# R141X.net
KiCad netlist of a schematic drawn in EAGLE
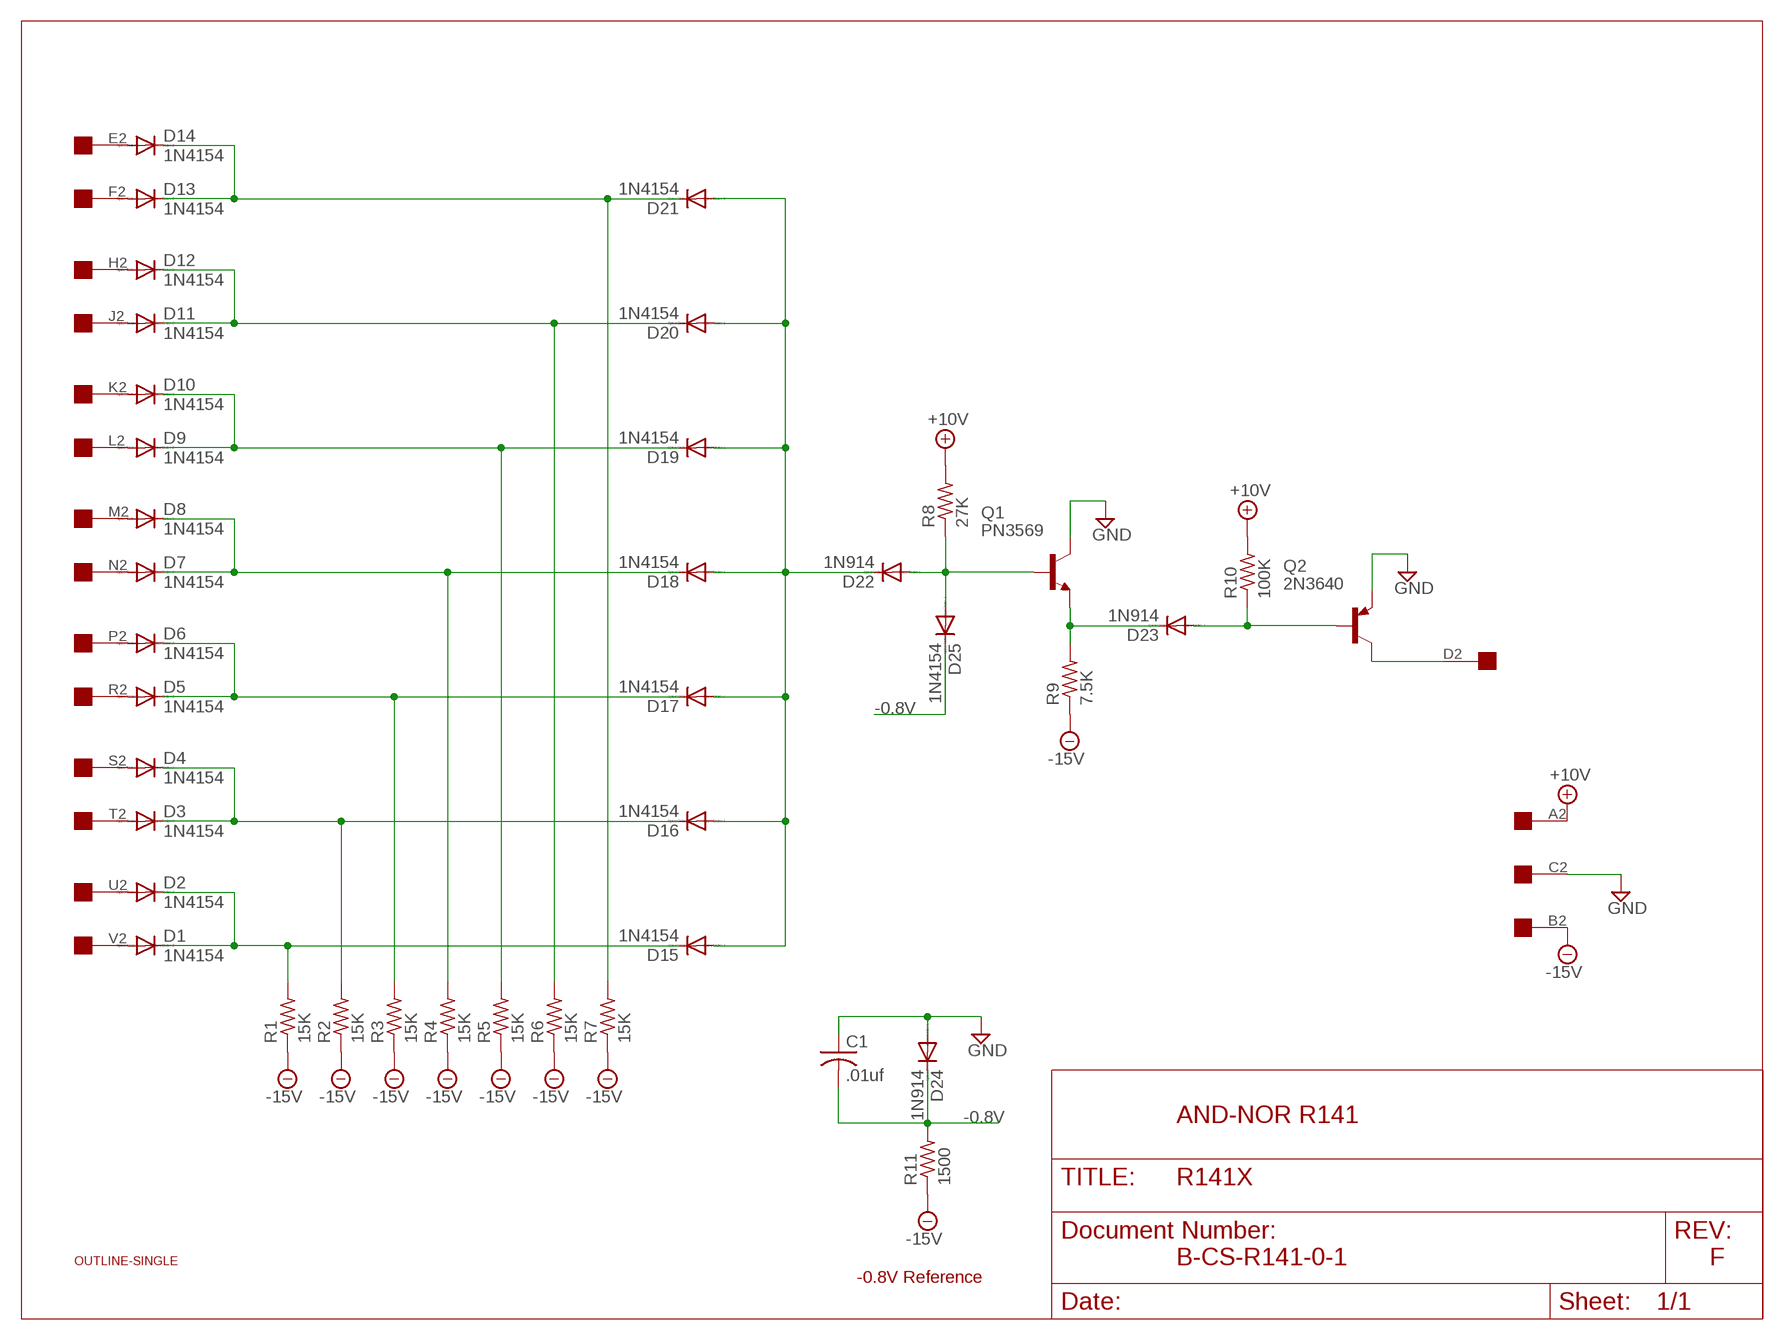
[diagram p0: schematic, sheet 1]

(export (version "E")
  (design (tool "Eeschema 10.0.6"))
  (components
    (comp (ref "C1")
      (value ".01uf")
      (footprint "eagle-import:C050-025X075")
      (libsource (lib "eagle-import") (part "C-US050-025X075"))
    )
    (comp (ref "D1")
      (value "1N4154")
      (footprint "eagle-import:DO35-10")
      (libsource (lib "eagle-import") (part "1N4148DO35-10"))
    )
    (comp (ref "D2")
      (value "1N4154")
      (footprint "eagle-import:DO35-10")
      (libsource (lib "eagle-import") (part "1N4148DO35-10"))
    )
    (comp (ref "D3")
      (value "1N4154")
      (footprint "eagle-import:DO35-10")
      (libsource (lib "eagle-import") (part "1N4148DO35-10"))
    )
    (comp (ref "D4")
      (value "1N4154")
      (footprint "eagle-import:DO35-10")
      (libsource (lib "eagle-import") (part "1N4148DO35-10"))
    )
    (comp (ref "D5")
      (value "1N4154")
      (footprint "eagle-import:DO35-10")
      (libsource (lib "eagle-import") (part "1N4148DO35-10"))
    )
    (comp (ref "D6")
      (value "1N4154")
      (footprint "eagle-import:DO35-10")
      (libsource (lib "eagle-import") (part "1N4148DO35-10"))
    )
    (comp (ref "D7")
      (value "1N4154")
      (footprint "eagle-import:DO35-10")
      (libsource (lib "eagle-import") (part "1N4148DO35-10"))
    )
    (comp (ref "D8")
      (value "1N4154")
      (footprint "eagle-import:DO35-10")
      (libsource (lib "eagle-import") (part "1N4148DO35-10"))
    )
    (comp (ref "D9")
      (value "1N4154")
      (footprint "eagle-import:DO35-10")
      (libsource (lib "eagle-import") (part "1N4148DO35-10"))
    )
    (comp (ref "D10")
      (value "1N4154")
      (footprint "eagle-import:DO35-10")
      (libsource (lib "eagle-import") (part "1N4148DO35-10"))
    )
    (comp (ref "D11")
      (value "1N4154")
      (footprint "eagle-import:DO35-10")
      (libsource (lib "eagle-import") (part "1N4148DO35-10"))
    )
    (comp (ref "D12")
      (value "1N4154")
      (footprint "eagle-import:DO35-10")
      (libsource (lib "eagle-import") (part "1N4148DO35-10"))
    )
    (comp (ref "D13")
      (value "1N4154")
      (footprint "eagle-import:DO35-10")
      (libsource (lib "eagle-import") (part "1N4148DO35-10"))
    )
    (comp (ref "D14")
      (value "1N4154")
      (footprint "eagle-import:DO35-10")
      (libsource (lib "eagle-import") (part "1N4148DO35-10"))
    )
    (comp (ref "D15")
      (value "1N4154")
      (footprint "eagle-import:DO35-10")
      (libsource (lib "eagle-import") (part "1N4148DO35-10"))
    )
    (comp (ref "D16")
      (value "1N4154")
      (footprint "eagle-import:DO35-10")
      (libsource (lib "eagle-import") (part "1N4148DO35-10"))
    )
    (comp (ref "D17")
      (value "1N4154")
      (footprint "eagle-import:DO35-10")
      (libsource (lib "eagle-import") (part "1N4148DO35-10"))
    )
    (comp (ref "D18")
      (value "1N4154")
      (footprint "eagle-import:DO35-10")
      (libsource (lib "eagle-import") (part "1N4148DO35-10"))
    )
    (comp (ref "D19")
      (value "1N4154")
      (footprint "eagle-import:DO35-10")
      (libsource (lib "eagle-import") (part "1N4148DO35-10"))
    )
    (comp (ref "D20")
      (value "1N4154")
      (footprint "eagle-import:DO35-10")
      (libsource (lib "eagle-import") (part "1N4148DO35-10"))
    )
    (comp (ref "D21")
      (value "1N4154")
      (footprint "eagle-import:DO35-10")
      (libsource (lib "eagle-import") (part "1N4148DO35-10"))
    )
    (comp (ref "D22")
      (value "1N914")
      (footprint "eagle-import:DO35-10")
      (libsource (lib "eagle-import") (part "1N4148DO35-10"))
    )
    (comp (ref "D23")
      (value "1N914")
      (footprint "eagle-import:DO35-10")
      (libsource (lib "eagle-import") (part "1N4148DO35-10"))
    )
    (comp (ref "D24")
      (value "1N914")
      (footprint "eagle-import:DO35-10")
      (libsource (lib "eagle-import") (part "1N4148DO35-10"))
    )
    (comp (ref "D25")
      (value "1N4154")
      (footprint "eagle-import:DO35-10")
      (libsource (lib "eagle-import") (part "1N4148DO35-10"))
    )
    (comp (ref "Q1")
      (value "PN3569")
      (footprint "eagle-import:TO39")
      (libsource (lib "eagle-import") (part "-NPN-TO39-EBC2N3019"))
    )
    (comp (ref "Q2")
      (value "2N3640")
      (footprint "eagle-import:TO39")
      (libsource (lib "eagle-import") (part "2N3637"))
    )
    (comp (ref "R1")
      (value "15K")
      (footprint "eagle-import:0207_10")
      (libsource (lib "eagle-import") (part "R-US_0207/10"))
    )
    (comp (ref "R2")
      (value "15K")
      (footprint "eagle-import:0207_10")
      (libsource (lib "eagle-import") (part "R-US_0207/10"))
    )
    (comp (ref "R3")
      (value "15K")
      (footprint "eagle-import:0207_10")
      (libsource (lib "eagle-import") (part "R-US_0207/10"))
    )
    (comp (ref "R4")
      (value "15K")
      (footprint "eagle-import:0207_10")
      (libsource (lib "eagle-import") (part "R-US_0207/10"))
    )
    (comp (ref "R5")
      (value "15K")
      (footprint "eagle-import:0207_10")
      (libsource (lib "eagle-import") (part "R-US_0207/10"))
    )
    (comp (ref "R6")
      (value "15K")
      (footprint "eagle-import:0207_10")
      (libsource (lib "eagle-import") (part "R-US_0207/10"))
    )
    (comp (ref "R7")
      (value "15K")
      (footprint "eagle-import:0207_10")
      (libsource (lib "eagle-import") (part "R-US_0207/10"))
    )
    (comp (ref "R8")
      (value "27K")
      (footprint "eagle-import:0207_10")
      (libsource (lib "eagle-import") (part "R-US_0207/10"))
    )
    (comp (ref "R9")
      (value "7.5K")
      (footprint "eagle-import:0207_10")
      (libsource (lib "eagle-import") (part "R-US_0207/10"))
    )
    (comp (ref "R10")
      (value "100K")
      (footprint "eagle-import:0207_10")
      (libsource (lib "eagle-import") (part "R-US_0207/10"))
    )
    (comp (ref "R11")
      (value "1500")
      (footprint "eagle-import:0207_10")
      (libsource (lib "eagle-import") (part "R-US_0207/10"))
    )
    (comp (ref "U$1")
      (value "OUTLINE-SINGLE")
      (footprint "eagle-import:SINGLE")
      (libsource (lib "eagle-import") (part "OUTLINE-SINGLE"))
    )
    (comp (ref "U$2")
      (value "EDGE-1")
      (footprint "eagle-import:EDGE-CON1")
      (libsource (lib "eagle-import") (part "EDGE-1"))
    )
  )
  (nets
    (net (code "1") (name "+10V") (class "Default")
      (node (ref "R10") (pin "2") (pinfunction "2_2") (pintype "passive"))
      (node (ref "R8") (pin "2") (pinfunction "2_2") (pintype "passive"))
      (node (ref "U$2") (pin "A2") (pinfunction "1_A2") (pintype "bidirectional"))
    )
    (net (code "2") (name "-15V") (class "Default")
      (node (ref "R1") (pin "1") (pinfunction "1_1") (pintype "passive"))
      (node (ref "R11") (pin "1") (pinfunction "1_1") (pintype "passive"))
      (node (ref "R2") (pin "1") (pinfunction "1_1") (pintype "passive"))
      (node (ref "R3") (pin "1") (pinfunction "1_1") (pintype "passive"))
      (node (ref "R4") (pin "1") (pinfunction "1_1") (pintype "passive"))
      (node (ref "R5") (pin "1") (pinfunction "1_1") (pintype "passive"))
      (node (ref "R6") (pin "1") (pinfunction "1_1") (pintype "passive"))
      (node (ref "R7") (pin "1") (pinfunction "1_1") (pintype "passive"))
      (node (ref "R9") (pin "1") (pinfunction "1_1") (pintype "passive"))
      (node (ref "U$2") (pin "B2") (pinfunction "1_B2") (pintype "bidirectional"))
    )
    (net (code "3") (name "/-0.8V") (class "Default")
      (node (ref "C1") (pin "2") (pinfunction "2_2") (pintype "passive"))
      (node (ref "D24") (pin "C") (pinfunction "C_C") (pintype "passive"))
      (node (ref "D25") (pin "C") (pinfunction "C_C") (pintype "passive"))
      (node (ref "R11") (pin "2") (pinfunction "2_2") (pintype "passive"))
    )
    (net (code "4") (name "GND") (class "Default")
      (node (ref "C1") (pin "1") (pinfunction "1_1") (pintype "passive"))
      (node (ref "D24") (pin "A") (pinfunction "A_A") (pintype "passive"))
      (node (ref "Q1") (pin "3") (pinfunction "C_3") (pintype "passive"))
      (node (ref "Q2") (pin "1") (pinfunction "E_1") (pintype "passive"))
      (node (ref "U$2") (pin "C2") (pinfunction "1_C2") (pintype "bidirectional"))
    )
    (net (code "5") (name "Net-(D1-PadC)") (class "Default")
      (node (ref "D1") (pin "C") (pinfunction "C_C") (pintype "passive"))
      (node (ref "D15") (pin "C") (pinfunction "C_C") (pintype "passive"))
      (node (ref "D2") (pin "C") (pinfunction "C_C") (pintype "passive"))
      (node (ref "R1") (pin "2") (pinfunction "2_2") (pintype "passive"))
    )
    (net (code "6") (name "Net-(D10-PadC)") (class "Default")
      (node (ref "D10") (pin "C") (pinfunction "C_C") (pintype "passive"))
      (node (ref "D19") (pin "C") (pinfunction "C_C") (pintype "passive"))
      (node (ref "D9") (pin "C") (pinfunction "C_C") (pintype "passive"))
      (node (ref "R5") (pin "2") (pinfunction "2_2") (pintype "passive"))
    )
    (net (code "7") (name "Net-(D11-PadC)") (class "Default")
      (node (ref "D11") (pin "C") (pinfunction "C_C") (pintype "passive"))
      (node (ref "D12") (pin "C") (pinfunction "C_C") (pintype "passive"))
      (node (ref "D20") (pin "C") (pinfunction "C_C") (pintype "passive"))
      (node (ref "R6") (pin "2") (pinfunction "2_2") (pintype "passive"))
    )
    (net (code "8") (name "Net-(D13-PadC)") (class "Default")
      (node (ref "D13") (pin "C") (pinfunction "C_C") (pintype "passive"))
      (node (ref "D14") (pin "C") (pinfunction "C_C") (pintype "passive"))
      (node (ref "D21") (pin "C") (pinfunction "C_C") (pintype "passive"))
      (node (ref "R7") (pin "2") (pinfunction "2_2") (pintype "passive"))
    )
    (net (code "9") (name "Net-(D15-PadA)") (class "Default")
      (node (ref "D15") (pin "A") (pinfunction "A_A") (pintype "passive"))
      (node (ref "D16") (pin "A") (pinfunction "A_A") (pintype "passive"))
      (node (ref "D17") (pin "A") (pinfunction "A_A") (pintype "passive"))
      (node (ref "D18") (pin "A") (pinfunction "A_A") (pintype "passive"))
      (node (ref "D19") (pin "A") (pinfunction "A_A") (pintype "passive"))
      (node (ref "D20") (pin "A") (pinfunction "A_A") (pintype "passive"))
      (node (ref "D21") (pin "A") (pinfunction "A_A") (pintype "passive"))
      (node (ref "D22") (pin "C") (pinfunction "C_C") (pintype "passive"))
    )
    (net (code "10") (name "Net-(D16-PadC)") (class "Default")
      (node (ref "D16") (pin "C") (pinfunction "C_C") (pintype "passive"))
      (node (ref "D3") (pin "C") (pinfunction "C_C") (pintype "passive"))
      (node (ref "D4") (pin "C") (pinfunction "C_C") (pintype "passive"))
      (node (ref "R2") (pin "2") (pinfunction "2_2") (pintype "passive"))
    )
    (net (code "11") (name "Net-(D17-PadC)") (class "Default")
      (node (ref "D17") (pin "C") (pinfunction "C_C") (pintype "passive"))
      (node (ref "D5") (pin "C") (pinfunction "C_C") (pintype "passive"))
      (node (ref "D6") (pin "C") (pinfunction "C_C") (pintype "passive"))
      (node (ref "R3") (pin "2") (pinfunction "2_2") (pintype "passive"))
    )
    (net (code "12") (name "Net-(D18-PadC)") (class "Default")
      (node (ref "D18") (pin "C") (pinfunction "C_C") (pintype "passive"))
      (node (ref "D7") (pin "C") (pinfunction "C_C") (pintype "passive"))
      (node (ref "D8") (pin "C") (pinfunction "C_C") (pintype "passive"))
      (node (ref "R4") (pin "2") (pinfunction "2_2") (pintype "passive"))
    )
    (net (code "13") (name "Net-(Q1-B)") (class "Default")
      (node (ref "D22") (pin "A") (pinfunction "A_A") (pintype "passive"))
      (node (ref "D25") (pin "A") (pinfunction "A_A") (pintype "passive"))
      (node (ref "Q1") (pin "2") (pinfunction "B_2") (pintype "passive"))
      (node (ref "R8") (pin "1") (pinfunction "1_1") (pintype "passive"))
    )
    (net (code "14") (name "Net-(Q1-E)") (class "Default")
      (node (ref "D23") (pin "C") (pinfunction "C_C") (pintype "passive"))
      (node (ref "Q1") (pin "1") (pinfunction "E_1") (pintype "passive"))
      (node (ref "R9") (pin "2") (pinfunction "2_2") (pintype "passive"))
    )
    (net (code "15") (name "Net-(Q2-B)") (class "Default")
      (node (ref "D23") (pin "A") (pinfunction "A_A") (pintype "passive"))
      (node (ref "Q2") (pin "2") (pinfunction "B_2") (pintype "passive"))
      (node (ref "R10") (pin "1") (pinfunction "1_1") (pintype "passive"))
    )
    (net (code "16") (name "Net-(Q2-C)") (class "Default")
      (node (ref "Q2") (pin "3") (pinfunction "C_3") (pintype "passive"))
      (node (ref "U$2") (pin "D2") (pinfunction "1_D2") (pintype "bidirectional"))
    )
    (net (code "17") (name "Net-(U$2E-1)") (class "Default")
      (node (ref "D14") (pin "A") (pinfunction "A_A") (pintype "passive"))
      (node (ref "U$2") (pin "E2") (pinfunction "1_E2") (pintype "bidirectional"))
    )
    (net (code "18") (name "Net-(U$2F-1)") (class "Default")
      (node (ref "D13") (pin "A") (pinfunction "A_A") (pintype "passive"))
      (node (ref "U$2") (pin "F2") (pinfunction "1_F2") (pintype "bidirectional"))
    )
    (net (code "19") (name "Net-(U$2G-1)") (class "Default")
      (node (ref "D12") (pin "A") (pinfunction "A_A") (pintype "passive"))
      (node (ref "U$2") (pin "H2") (pinfunction "1_H2") (pintype "bidirectional"))
    )
    (net (code "20") (name "Net-(U$2H-1)") (class "Default")
      (node (ref "D11") (pin "A") (pinfunction "A_A") (pintype "passive"))
      (node (ref "U$2") (pin "J2") (pinfunction "1_J2") (pintype "bidirectional"))
    )
    (net (code "21") (name "Net-(U$2I-1)") (class "Default")
      (node (ref "D10") (pin "A") (pinfunction "A_A") (pintype "passive"))
      (node (ref "U$2") (pin "K2") (pinfunction "1_K2") (pintype "bidirectional"))
    )
    (net (code "22") (name "Net-(U$2J-1)") (class "Default")
      (node (ref "D9") (pin "A") (pinfunction "A_A") (pintype "passive"))
      (node (ref "U$2") (pin "L2") (pinfunction "1_L2") (pintype "bidirectional"))
    )
    (net (code "23") (name "Net-(U$2K-1)") (class "Default")
      (node (ref "D8") (pin "A") (pinfunction "A_A") (pintype "passive"))
      (node (ref "U$2") (pin "M2") (pinfunction "1_M2") (pintype "bidirectional"))
    )
    (net (code "24") (name "Net-(U$2L-1)") (class "Default")
      (node (ref "D7") (pin "A") (pinfunction "A_A") (pintype "passive"))
      (node (ref "U$2") (pin "N2") (pinfunction "1_N2") (pintype "bidirectional"))
    )
    (net (code "25") (name "Net-(U$2M-1)") (class "Default")
      (node (ref "D6") (pin "A") (pinfunction "A_A") (pintype "passive"))
      (node (ref "U$2") (pin "P2") (pinfunction "1_P2") (pintype "bidirectional"))
    )
    (net (code "26") (name "Net-(U$2N-1)") (class "Default")
      (node (ref "D5") (pin "A") (pinfunction "A_A") (pintype "passive"))
      (node (ref "U$2") (pin "R2") (pinfunction "1_R2") (pintype "bidirectional"))
    )
    (net (code "27") (name "Net-(U$2O-1)") (class "Default")
      (node (ref "D4") (pin "A") (pinfunction "A_A") (pintype "passive"))
      (node (ref "U$2") (pin "S2") (pinfunction "1_S2") (pintype "bidirectional"))
    )
    (net (code "28") (name "Net-(U$2P-1)") (class "Default")
      (node (ref "D3") (pin "A") (pinfunction "A_A") (pintype "passive"))
      (node (ref "U$2") (pin "T2") (pinfunction "1_T2") (pintype "bidirectional"))
    )
    (net (code "29") (name "Net-(U$2Q-1)") (class "Default")
      (node (ref "D2") (pin "A") (pinfunction "A_A") (pintype "passive"))
      (node (ref "U$2") (pin "U2") (pinfunction "1_U2") (pintype "bidirectional"))
    )
    (net (code "30") (name "Net-(U$2R-1)") (class "Default")
      (node (ref "D1") (pin "A") (pinfunction "A_A") (pintype "passive"))
      (node (ref "U$2") (pin "V2") (pinfunction "1_V2") (pintype "bidirectional"))
    )
  )
)
